# main.net
KiCad netlist of a schematic drawn in Altium Designer
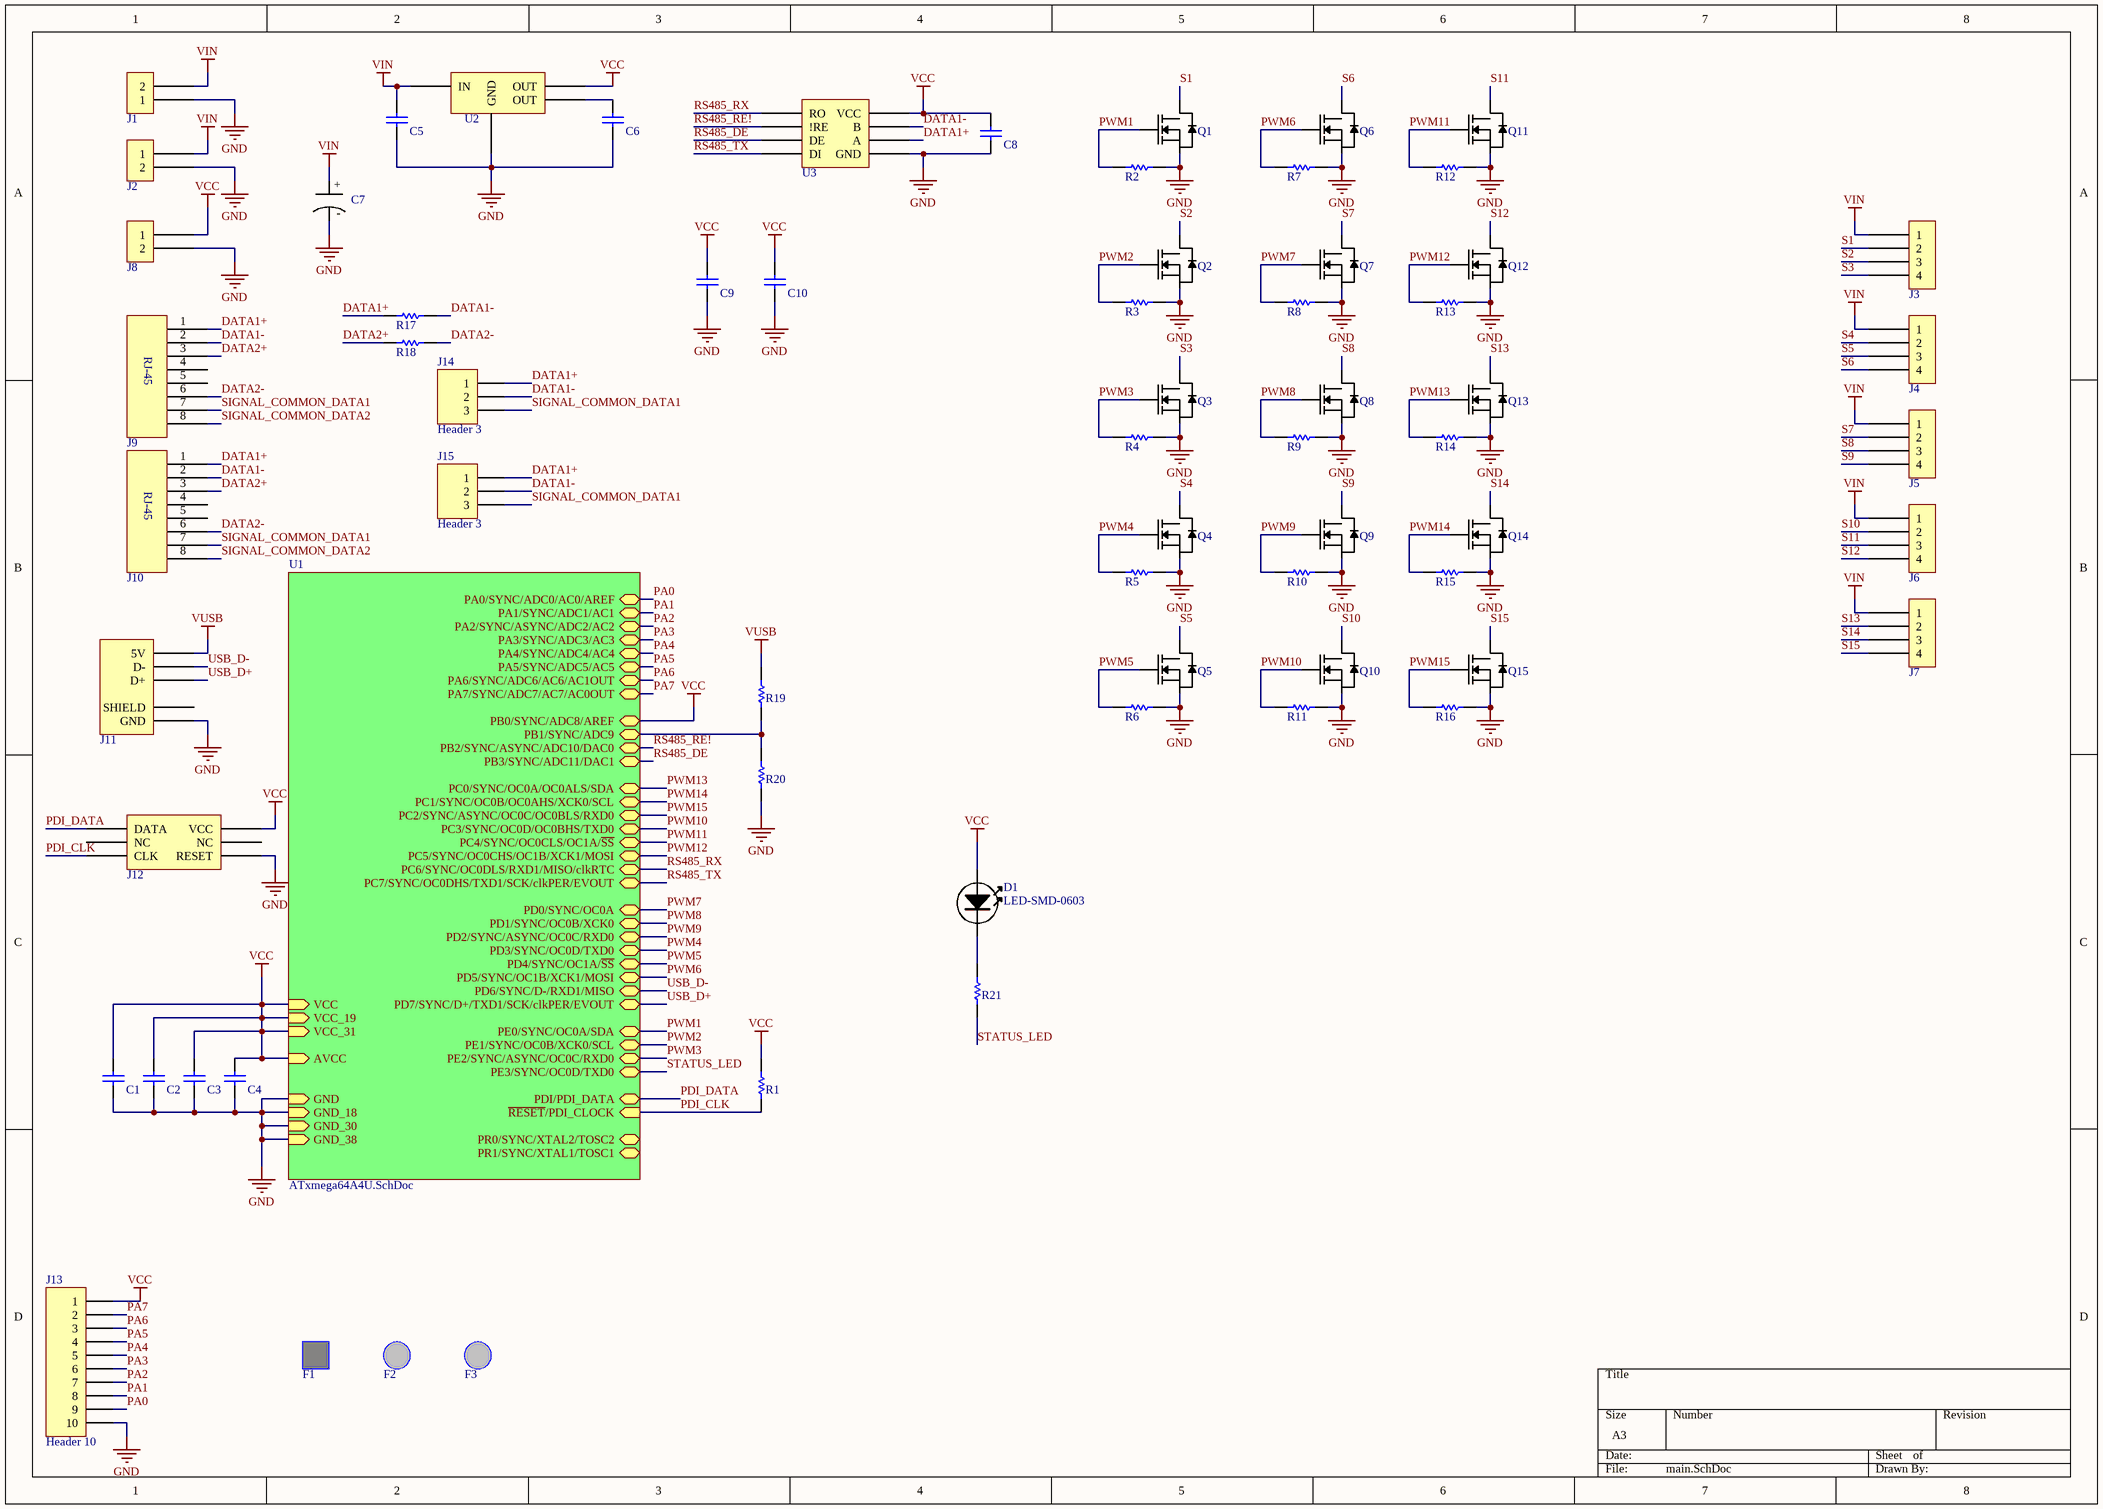
[diagram p0: main.SchDoc]

(export (version "E")
  (design (tool "Eeschema 10.0.6"))
  (components
    (comp (ref "C1")
      (value "CAP 3.3nF 10V 0805(2012)")
      (footprint "CAPC0805(2012)145_M")
      (description "CAP 3.3nF 10V ±1% 0805 (2012 Metric) Thickness 1.45mm SMD")
      (fields (field (name "TOLERANCE") "±1%"))
      (libsource (lib "Altium Content Vault") (part "CAP"))
    )
    (comp (ref "C2")
      (value "CAP 3.3nF 10V 0805(2012)")
      (footprint "CAPC0805(2012)145_M")
      (description "CAP 3.3nF 10V ±1% 0805 (2012 Metric) Thickness 1.45mm SMD")
      (fields (field (name "TOLERANCE") "±1%"))
      (libsource (lib "Altium Content Vault") (part "CAP"))
    )
    (comp (ref "C3")
      (value "CAP 3.3nF 10V 0805(2012)")
      (footprint "CAPC0805(2012)145_M")
      (description "CAP 3.3nF 10V ±1% 0805 (2012 Metric) Thickness 1.45mm SMD")
      (fields (field (name "TOLERANCE") "±1%"))
      (libsource (lib "Altium Content Vault") (part "CAP"))
    )
    (comp (ref "C4")
      (value "CAP 3.3nF 10V 0805(2012)")
      (footprint "CAPC0805(2012)145_M")
      (description "CAP 3.3nF 10V ±1% 0805 (2012 Metric) Thickness 1.45mm SMD")
      (fields (field (name "TOLERANCE") "±1%"))
      (libsource (lib "Altium Content Vault") (part "CAP"))
    )
    (comp (ref "C5")
      (value "CAP 1uF 16V 1210(3225)")
      (footprint "CAPC1210(3225)155_N")
      (description "CAP 1uF 16V ±5% 1210 (3225 Metric) Thickness 1.45mm SMD")
      (fields (field (name "TOLERANCE") "±5%"))
      (libsource (lib "Altium Content Vault") (part "CAP"))
    )
    (comp (ref "C6")
      (value "CAP 10uF 6.3V 1210(3225)")
      (footprint "CAPC1210(3225)170_L")
      (description "CAP 10uF 6.3V ±10% 1210 (3225 Metric) Thickness 1.7mm SMD")
      (fields (field (name "TOLERANCE") "±10%"))
      (libsource (lib "Altium Content Vault") (part "CAP"))
    )
    (comp (ref "C7")
      (value "ELECTROLYTIC-CAP-220uF")
      (footprint "ELECTROLYTIC-220uF")
      (libsource (lib "capacitors") (part "ELECTROLYTIC-CAP-220uF"))
    )
    (comp (ref "C8")
      (value "CAP 3.3nF 10V 0805(2012)")
      (footprint "CAPC0805(2012)145_M")
      (description "CAP 3.3nF 10V ±1% 0805 (2012 Metric) Thickness 1.45mm SMD")
      (fields (field (name "TOLERANCE") "±1%"))
      (libsource (lib "Altium Content Vault") (part "CAP"))
    )
    (comp (ref "C9")
      (value "CAP 10uF 6.3V 1210(3225)")
      (footprint "CAPC1210(3225)170_L")
      (description "CAP 10uF 6.3V ±10% 1210 (3225 Metric) Thickness 1.7mm SMD")
      (fields (field (name "TOLERANCE") "±10%"))
      (libsource (lib "Altium Content Vault") (part "CMP-1038-02188-1"))
    )
    (comp (ref "C10")
      (value "CAP 10uF 6.3V 1210(3225)")
      (footprint "CAPC1210(3225)170_L")
      (description "CAP 10uF 6.3V ±10% 1210 (3225 Metric) Thickness 1.7mm SMD")
      (fields (field (name "TOLERANCE") "±10%"))
      (libsource (lib "Altium Content Vault") (part "CMP-1038-02188-1"))
    )
    (comp (ref "D1")
      (value "LED-SMD-0603")
      (footprint "LED-0603")
      (description "SMD Led 0603")
      (libsource (lib "Omegav Vault") (part "LED-0603"))
    )
    (comp (ref "F1")
      (value "Fiducial square")
      (footprint "FIDU-SQUARE")
      (libsource (lib "fiducials") (part "FIDUCIAL_SQUARE"))
    )
    (comp (ref "F2")
      (value "Fiducial round")
      (footprint "FIDU-ROUND")
      (libsource (lib "fiducials") (part "FIDUCIAL_ROUND"))
    )
    (comp (ref "F3")
      (value "Fiducial round")
      (footprint "FIDU-ROUND")
      (libsource (lib "fiducials") (part "FIDUCIAL_ROUND"))
    )
    (comp (ref "J1")
      (value "PLUGGABLE-TERMINAL-2")
      (footprint "PLUG_TERMINAL_2")
      (libsource (lib "") (part "PLUGGABLE-TERMINAL-2_1"))
    )
    (comp (ref "J2")
      (value "PLUGGABLE-TERMINAL-2")
      (footprint "PLUG_TERMINAL_2")
      (libsource (lib "connectors") (part "PLUGGABLE-TERMINAL-2"))
    )
    (comp (ref "J3")
      (value "PLUGGABLE-TERMINAL-4")
      (footprint "PLUG_TERMINAL_4")
      (libsource (lib "connectors") (part "PLUGGABLE-TERMINAL-4"))
    )
    (comp (ref "J4")
      (value "PLUGGABLE-TERMINAL-4")
      (footprint "PLUG_TERMINAL_4")
      (libsource (lib "connectors") (part "PLUGGABLE-TERMINAL-4"))
    )
    (comp (ref "J5")
      (value "PLUGGABLE-TERMINAL-4")
      (footprint "PLUG_TERMINAL_4")
      (libsource (lib "connectors") (part "PLUGGABLE-TERMINAL-4"))
    )
    (comp (ref "J6")
      (value "PLUGGABLE-TERMINAL-4")
      (footprint "PLUG_TERMINAL_4")
      (libsource (lib "connectors") (part "PLUGGABLE-TERMINAL-4"))
    )
    (comp (ref "J7")
      (value "PLUGGABLE-TERMINAL-4")
      (footprint "PLUG_TERMINAL_4")
      (libsource (lib "connectors") (part "PLUGGABLE-TERMINAL-4"))
    )
    (comp (ref "J8")
      (value "PLUGGABLE-TERMINAL-2")
      (footprint "PLUG_TERMINAL_2")
      (libsource (lib "connectors") (part "PLUGGABLE-TERMINAL-2"))
    )
    (comp (ref "J9")
      (value "RJ-45 Connector")
      (footprint "RJ-45")
      (description "RJ-45 Ethernet Connector")
      (fields (field (name "TOLERANCE") "1"))
      (libsource (lib "Omegav Vault") (part "RJ-45"))
    )
    (comp (ref "J10")
      (value "RJ-45 Connector")
      (footprint "RJ-45")
      (description "RJ-45 Ethernet Connector")
      (fields (field (name "TOLERANCE") "1"))
      (libsource (lib "Omegav Vault") (part "RJ-45"))
    )
    (comp (ref "J11")
      (value "USB-MINI")
      (footprint "USB-mini")
      (description "USB-Mini Connector")
      (fields (field (name "TOLERANCE") "1"))
      (libsource (lib "Omegav Vault") (part "USB-mini"))
    )
    (comp (ref "J12")
      (value "PDI")
      (footprint "HEADER_SMD_3x2_50MIL")
      (libsource (lib "connectors") (part "PDI"))
    )
    (comp (ref "J13")
      (value "Header 10")
      (footprint "HDR1X10")
      (description "Header, 10-Pin")
      (fields (field (name "PUBLISHER") "Altium Limited"))
      (libsource (lib "Miscellaneous Connectors") (part "Header 10"))
    )
    (comp (ref "J14")
      (value "Header 3")
      (footprint "HDR1X3")
      (description "Header, 3-Pin")
      (fields (field (name "PUBLISHER") "Altium Limited"))
      (libsource (lib "Miscellaneous Connectors") (part "Header 3"))
    )
    (comp (ref "J15")
      (value "Header 3")
      (footprint "HDR1X3")
      (description "Header, 3-Pin")
      (fields (field (name "PUBLISHER") "Altium Limited"))
      (libsource (lib "Miscellaneous Connectors") (part "Header 3"))
    )
    (comp (ref "Q1")
      (value "TSM2314CX")
      (footprint "SOT95P280X130-3N")
      (description "MOSFET 4.9A max switching load")
      (libsource (lib "transistors") (part "TSM2314CX"))
    )
    (comp (ref "Q2")
      (value "TSM2314CX")
      (footprint "SOT95P280X130-3N")
      (description "MOSFET 4.9A max switching load")
      (libsource (lib "transistors") (part "TSM2314CX"))
    )
    (comp (ref "Q3")
      (value "TSM2314CX")
      (footprint "SOT95P280X130-3N")
      (description "MOSFET 4.9A max switching load")
      (libsource (lib "transistors") (part "TSM2314CX"))
    )
    (comp (ref "Q4")
      (value "TSM2314CX")
      (footprint "SOT95P280X130-3N")
      (description "MOSFET 4.9A max switching load")
      (libsource (lib "transistors") (part "TSM2314CX"))
    )
    (comp (ref "Q5")
      (value "TSM2314CX")
      (footprint "SOT95P280X130-3N")
      (description "MOSFET 4.9A max switching load")
      (libsource (lib "transistors") (part "TSM2314CX"))
    )
    (comp (ref "Q6")
      (value "TSM2314CX")
      (footprint "SOT95P280X130-3N")
      (description "MOSFET 4.9A max switching load")
      (libsource (lib "transistors") (part "TSM2314CX"))
    )
    (comp (ref "Q7")
      (value "TSM2314CX")
      (footprint "SOT95P280X130-3N")
      (description "MOSFET 4.9A max switching load")
      (libsource (lib "transistors") (part "TSM2314CX"))
    )
    (comp (ref "Q8")
      (value "TSM2314CX")
      (footprint "SOT95P280X130-3N")
      (description "MOSFET 4.9A max switching load")
      (libsource (lib "transistors") (part "TSM2314CX"))
    )
    (comp (ref "Q9")
      (value "TSM2314CX")
      (footprint "SOT95P280X130-3N")
      (description "MOSFET 4.9A max switching load")
      (libsource (lib "transistors") (part "TSM2314CX"))
    )
    (comp (ref "Q10")
      (value "TSM2314CX")
      (footprint "SOT95P280X130-3N")
      (description "MOSFET 4.9A max switching load")
      (libsource (lib "transistors") (part "TSM2314CX"))
    )
    (comp (ref "Q11")
      (value "TSM2314CX")
      (footprint "SOT95P280X130-3N")
      (description "MOSFET 4.9A max switching load")
      (libsource (lib "transistors") (part "TSM2314CX"))
    )
    (comp (ref "Q12")
      (value "TSM2314CX")
      (footprint "SOT95P280X130-3N")
      (description "MOSFET 4.9A max switching load")
      (libsource (lib "transistors") (part "TSM2314CX"))
    )
    (comp (ref "Q13")
      (value "TSM2314CX")
      (footprint "SOT95P280X130-3N")
      (description "MOSFET 4.9A max switching load")
      (libsource (lib "transistors") (part "TSM2314CX"))
    )
    (comp (ref "Q14")
      (value "TSM2314CX")
      (footprint "SOT95P280X130-3N")
      (description "MOSFET 4.9A max switching load")
      (libsource (lib "transistors") (part "TSM2314CX"))
    )
    (comp (ref "Q15")
      (value "TSM2314CX")
      (footprint "SOT95P280X130-3N")
      (description "MOSFET 4.9A max switching load")
      (libsource (lib "transistors") (part "TSM2314CX"))
    )
    (comp (ref "R1")
      (value "10K 1% 0805(2012)")
      (footprint "RESC0805(2012)_M")
      (description "10K 0.125W 1% 0805 (2012 Metric)  SMD")
      (fields (field (name "TOLERANCE") "1 %") (field (name "POWER") "0.125 W"))
      (libsource (lib "Altium Content Vault") (part "RES"))
    )
    (comp (ref "R2")
      (value "10K 1% 0805(2012)")
      (footprint "RESC0805(2012)_M")
      (description "10K 0.125W 1% 0805 (2012 Metric)  SMD")
      (fields (field (name "TOLERANCE") "1 %") (field (name "POWER") "0.125 W"))
      (libsource (lib "Altium Content Vault") (part "RES"))
    )
    (comp (ref "R3")
      (value "10K 1% 0805(2012)")
      (footprint "RESC0805(2012)_M")
      (description "10K 0.125W 1% 0805 (2012 Metric)  SMD")
      (fields (field (name "TOLERANCE") "1 %") (field (name "POWER") "0.125 W"))
      (libsource (lib "Altium Content Vault") (part "RES"))
    )
    (comp (ref "R4")
      (value "10K 1% 0805(2012)")
      (footprint "RESC0805(2012)_M")
      (description "10K 0.125W 1% 0805 (2012 Metric)  SMD")
      (fields (field (name "TOLERANCE") "1 %") (field (name "POWER") "0.125 W"))
      (libsource (lib "Altium Content Vault") (part "RES"))
    )
    (comp (ref "R5")
      (value "10K 1% 0805(2012)")
      (footprint "RESC0805(2012)_M")
      (description "10K 0.125W 1% 0805 (2012 Metric)  SMD")
      (fields (field (name "TOLERANCE") "1 %") (field (name "POWER") "0.125 W"))
      (libsource (lib "Altium Content Vault") (part "RES"))
    )
    (comp (ref "R6")
      (value "10K 1% 0805(2012)")
      (footprint "RESC0805(2012)_M")
      (description "10K 0.125W 1% 0805 (2012 Metric)  SMD")
      (fields (field (name "TOLERANCE") "1 %") (field (name "POWER") "0.125 W"))
      (libsource (lib "Altium Content Vault") (part "RES"))
    )
    (comp (ref "R7")
      (value "10K 1% 0805(2012)")
      (footprint "RESC0805(2012)_M")
      (description "10K 0.125W 1% 0805 (2012 Metric)  SMD")
      (fields (field (name "TOLERANCE") "1 %") (field (name "POWER") "0.125 W"))
      (libsource (lib "Altium Content Vault") (part "RES"))
    )
    (comp (ref "R8")
      (value "10K 1% 0805(2012)")
      (footprint "RESC0805(2012)_M")
      (description "10K 0.125W 1% 0805 (2012 Metric)  SMD")
      (fields (field (name "TOLERANCE") "1 %") (field (name "POWER") "0.125 W"))
      (libsource (lib "Altium Content Vault") (part "RES"))
    )
    (comp (ref "R9")
      (value "10K 1% 0805(2012)")
      (footprint "RESC0805(2012)_M")
      (description "10K 0.125W 1% 0805 (2012 Metric)  SMD")
      (fields (field (name "TOLERANCE") "1 %") (field (name "POWER") "0.125 W"))
      (libsource (lib "Altium Content Vault") (part "RES"))
    )
    (comp (ref "R10")
      (value "10K 1% 0805(2012)")
      (footprint "RESC0805(2012)_M")
      (description "10K 0.125W 1% 0805 (2012 Metric)  SMD")
      (fields (field (name "TOLERANCE") "1 %") (field (name "POWER") "0.125 W"))
      (libsource (lib "Altium Content Vault") (part "RES"))
    )
    (comp (ref "R11")
      (value "10K 1% 0805(2012)")
      (footprint "RESC0805(2012)_M")
      (description "10K 0.125W 1% 0805 (2012 Metric)  SMD")
      (fields (field (name "TOLERANCE") "1 %") (field (name "POWER") "0.125 W"))
      (libsource (lib "Altium Content Vault") (part "RES"))
    )
    (comp (ref "R12")
      (value "10K 1% 0805(2012)")
      (footprint "RESC0805(2012)_M")
      (description "10K 0.125W 1% 0805 (2012 Metric)  SMD")
      (fields (field (name "TOLERANCE") "1 %") (field (name "POWER") "0.125 W"))
      (libsource (lib "Altium Content Vault") (part "RES"))
    )
    (comp (ref "R13")
      (value "10K 1% 0805(2012)")
      (footprint "RESC0805(2012)_M")
      (description "10K 0.125W 1% 0805 (2012 Metric)  SMD")
      (fields (field (name "TOLERANCE") "1 %") (field (name "POWER") "0.125 W"))
      (libsource (lib "Altium Content Vault") (part "RES"))
    )
    (comp (ref "R14")
      (value "10K 1% 0805(2012)")
      (footprint "RESC0805(2012)_M")
      (description "10K 0.125W 1% 0805 (2012 Metric)  SMD")
      (fields (field (name "TOLERANCE") "1 %") (field (name "POWER") "0.125 W"))
      (libsource (lib "Altium Content Vault") (part "RES"))
    )
    (comp (ref "R15")
      (value "10K 1% 0805(2012)")
      (footprint "RESC0805(2012)_M")
      (description "10K 0.125W 1% 0805 (2012 Metric)  SMD")
      (fields (field (name "TOLERANCE") "1 %") (field (name "POWER") "0.125 W"))
      (libsource (lib "Altium Content Vault") (part "RES"))
    )
    (comp (ref "R16")
      (value "10K 1% 0805(2012)")
      (footprint "RESC0805(2012)_M")
      (description "10K 0.125W 1% 0805 (2012 Metric)  SMD")
      (fields (field (name "TOLERANCE") "1 %") (field (name "POWER") "0.125 W"))
      (libsource (lib "Altium Content Vault") (part "RES"))
    )
    (comp (ref "R17")
      (value "120R 1% 0805(2012)")
      (footprint "RESC0805(2012)_M")
      (description "120R 0.125W 1% 0805 (2012 Metric)  SMD")
      (fields (field (name "TOLERANCE") "1 %") (field (name "POWER") "0.125 W"))
      (libsource (lib "Altium Content Vault") (part "RES"))
    )
    (comp (ref "R18")
      (value "120R 1% 0805(2012)")
      (footprint "RESC0805(2012)_M")
      (description "120R 0.125W 1% 0805 (2012 Metric)  SMD")
      (fields (field (name "TOLERANCE") "1 %") (field (name "POWER") "0.125 W"))
      (libsource (lib "Altium Content Vault") (part "RES"))
    )
    (comp (ref "R19")
      (value "10K 1% 0805(2012)")
      (footprint "RESC0805(2012)_M")
      (description "10K 0.125W 1% 0805 (2012 Metric)  SMD")
      (fields (field (name "TOLERANCE") "1 %") (field (name "POWER") "0.125 W"))
      (libsource (lib "Altium Content Vault") (part "RES"))
    )
    (comp (ref "R20")
      (value "15K 1% 0805(2012)")
      (footprint "RESC0805(2012)_L")
      (description "15K 0.125W 1% 0805 (2012 Metric)  SMD")
      (fields (field (name "POWER") "0.125 W") (field (name "TOLERANCE") "1 %"))
      (libsource (lib "Altium Content Vault") (part "RES"))
    )
    (comp (ref "R21")
      (value "200R 1% 0805(2012)")
      (footprint "RESC0805(2012)_L")
      (description "200R 0.125W 1% 0805 (2012 Metric)  SMD")
      (fields (field (name "POWER") "0.125 W") (field (name "TOLERANCE") "1 %"))
      (libsource (lib "Altium Content Vault") (part "RES"))
    )
    (comp (ref "U2")
      (value "TLV1117")
      (footprint "SOT230P700X180-4N")
      (description "3.3V Linear Regulator")
      (libsource (lib "Omegav Vault") (part "TLV1117"))
    )
    (comp (ref "U3")
      (value "MAX3485")
      (footprint "SOP127P600X175-8N")
      (libsource (lib "ics") (part "MAX3485"))
    )
  )
  (nets
    (net (code "1") (name "/DATA1+") (class "Default")
      (node (ref "J10") (pin "1") (pinfunction "1_1") (pintype "passive"))
      (node (ref "J14") (pin "1") (pinfunction "1_1") (pintype "passive"))
      (node (ref "J15") (pin "1") (pinfunction "1_1") (pintype "passive"))
      (node (ref "J9") (pin "1") (pinfunction "1_1") (pintype "passive"))
      (node (ref "R17") (pin "1") (pinfunction "1_1") (pintype "passive"))
      (node (ref "U3") (pin "6") (pinfunction "A_6") (pintype "passive"))
    )
    (net (code "2") (name "/DATA1-") (class "Default")
      (node (ref "J10") (pin "2") (pinfunction "2_2") (pintype "passive"))
      (node (ref "J14") (pin "2") (pinfunction "2_2") (pintype "passive"))
      (node (ref "J15") (pin "2") (pinfunction "2_2") (pintype "passive"))
      (node (ref "J9") (pin "2") (pinfunction "2_2") (pintype "passive"))
      (node (ref "R17") (pin "2") (pinfunction "2_2") (pintype "passive"))
      (node (ref "U3") (pin "7") (pinfunction "B_7") (pintype "passive"))
    )
    (net (code "3") (name "/DATA2+") (class "Default")
      (node (ref "J10") (pin "3") (pinfunction "3_3") (pintype "passive"))
      (node (ref "J9") (pin "3") (pinfunction "3_3") (pintype "passive"))
      (node (ref "R18") (pin "1") (pinfunction "1_1") (pintype "passive"))
    )
    (net (code "4") (name "/DATA2-") (class "Default")
      (node (ref "J10") (pin "6") (pinfunction "6_6") (pintype "passive"))
      (node (ref "J9") (pin "6") (pinfunction "6_6") (pintype "passive"))
      (node (ref "R18") (pin "2") (pinfunction "2_2") (pintype "passive"))
    )
    (net (code "5") (name "/PA0") (class "Default")
      (node (ref "J13") (pin "9") (pinfunction "9_9") (pintype "passive"))
    )
    (net (code "6") (name "/PA1") (class "Default")
      (node (ref "J13") (pin "8") (pinfunction "8_8") (pintype "passive"))
    )
    (net (code "7") (name "/PA2") (class "Default")
      (node (ref "J13") (pin "7") (pinfunction "7_7") (pintype "passive"))
    )
    (net (code "8") (name "/PA3") (class "Default")
      (node (ref "J13") (pin "6") (pinfunction "6_6") (pintype "passive"))
    )
    (net (code "9") (name "/PA4") (class "Default")
      (node (ref "J13") (pin "5") (pinfunction "5_5") (pintype "passive"))
    )
    (net (code "10") (name "/PA5") (class "Default")
      (node (ref "J13") (pin "4") (pinfunction "4_4") (pintype "passive"))
    )
    (net (code "11") (name "/PA6") (class "Default")
      (node (ref "J13") (pin "3") (pinfunction "3_3") (pintype "passive"))
    )
    (net (code "12") (name "/PA7") (class "Default")
      (node (ref "J13") (pin "2") (pinfunction "2_2") (pintype "passive"))
    )
    (net (code "13") (name "/PB1{slash}SYNC{slash}ADC9") (class "Default")
      (node (ref "R19") (pin "1") (pinfunction "1_1") (pintype "passive"))
      (node (ref "R20") (pin "2") (pinfunction "2_2") (pintype "passive"))
    )
    (net (code "14") (name "/PDI_CLK") (class "Default")
      (node (ref "J12") (pin "5") (pinfunction "CLK_5") (pintype "passive"))
      (node (ref "R1") (pin "1") (pinfunction "1_1") (pintype "passive"))
    )
    (net (code "15") (name "/PDI_DATA") (class "Default")
      (node (ref "J12") (pin "1") (pinfunction "DATA_1") (pintype "passive"))
    )
    (net (code "18") (name "/PWM1") (class "Default")
      (node (ref "Q1") (pin "1") (pinfunction "G_1") (pintype "passive"))
      (node (ref "R2") (pin "1") (pinfunction "1_1") (pintype "passive"))
    )
    (net (code "19") (name "/PWM2") (class "Default")
      (node (ref "Q2") (pin "1") (pinfunction "G_1") (pintype "passive"))
      (node (ref "R3") (pin "1") (pinfunction "1_1") (pintype "passive"))
    )
    (net (code "20") (name "/PWM3") (class "Default")
      (node (ref "Q3") (pin "1") (pinfunction "G_1") (pintype "passive"))
      (node (ref "R4") (pin "1") (pinfunction "1_1") (pintype "passive"))
    )
    (net (code "21") (name "/PWM4") (class "Default")
      (node (ref "Q4") (pin "1") (pinfunction "G_1") (pintype "passive"))
      (node (ref "R5") (pin "1") (pinfunction "1_1") (pintype "passive"))
    )
    (net (code "22") (name "/PWM5") (class "Default")
      (node (ref "Q5") (pin "1") (pinfunction "G_1") (pintype "passive"))
      (node (ref "R6") (pin "1") (pinfunction "1_1") (pintype "passive"))
    )
    (net (code "23") (name "/PWM6") (class "Default")
      (node (ref "Q6") (pin "1") (pinfunction "G_1") (pintype "passive"))
      (node (ref "R7") (pin "1") (pinfunction "1_1") (pintype "passive"))
    )
    (net (code "24") (name "/PWM7") (class "Default")
      (node (ref "Q7") (pin "1") (pinfunction "G_1") (pintype "passive"))
      (node (ref "R8") (pin "1") (pinfunction "1_1") (pintype "passive"))
    )
    (net (code "25") (name "/PWM8") (class "Default")
      (node (ref "Q8") (pin "1") (pinfunction "G_1") (pintype "passive"))
      (node (ref "R9") (pin "1") (pinfunction "1_1") (pintype "passive"))
    )
    (net (code "26") (name "/PWM9") (class "Default")
      (node (ref "Q9") (pin "1") (pinfunction "G_1") (pintype "passive"))
      (node (ref "R10") (pin "1") (pinfunction "1_1") (pintype "passive"))
    )
    (net (code "27") (name "/PWM10") (class "Default")
      (node (ref "Q10") (pin "1") (pinfunction "G_1") (pintype "passive"))
      (node (ref "R11") (pin "1") (pinfunction "1_1") (pintype "passive"))
    )
    (net (code "28") (name "/PWM11") (class "Default")
      (node (ref "Q11") (pin "1") (pinfunction "G_1") (pintype "passive"))
      (node (ref "R12") (pin "1") (pinfunction "1_1") (pintype "passive"))
    )
    (net (code "29") (name "/PWM12") (class "Default")
      (node (ref "Q12") (pin "1") (pinfunction "G_1") (pintype "passive"))
      (node (ref "R13") (pin "1") (pinfunction "1_1") (pintype "passive"))
    )
    (net (code "30") (name "/PWM13") (class "Default")
      (node (ref "Q13") (pin "1") (pinfunction "G_1") (pintype "passive"))
      (node (ref "R14") (pin "1") (pinfunction "1_1") (pintype "passive"))
    )
    (net (code "31") (name "/PWM14") (class "Default")
      (node (ref "Q14") (pin "1") (pinfunction "G_1") (pintype "passive"))
      (node (ref "R15") (pin "1") (pinfunction "1_1") (pintype "passive"))
    )
    (net (code "32") (name "/PWM15") (class "Default")
      (node (ref "Q15") (pin "1") (pinfunction "G_1") (pintype "passive"))
      (node (ref "R16") (pin "1") (pinfunction "1_1") (pintype "passive"))
    )
    (net (code "33") (name "/RS485_DE") (class "Default")
      (node (ref "U3") (pin "3") (pinfunction "DE_3") (pintype "passive"))
    )
    (net (code "34") (name "/RS485_RE!") (class "Default")
      (node (ref "U3") (pin "2") (pinfunction "!RE_2") (pintype "passive"))
    )
    (net (code "35") (name "/RS485_RX") (class "Default")
      (node (ref "U3") (pin "1") (pinfunction "RO_1") (pintype "passive"))
    )
    (net (code "36") (name "/RS485_TX") (class "Default")
      (node (ref "U3") (pin "4") (pinfunction "DI_4") (pintype "passive"))
    )
    (net (code "37") (name "/S1") (class "Default")
      (node (ref "J3") (pin "2") (pinfunction "2_2") (pintype "passive"))
      (node (ref "Q1") (pin "3") (pinfunction "D_3") (pintype "passive"))
    )
    (net (code "38") (name "/S2") (class "Default")
      (node (ref "J3") (pin "3") (pinfunction "3_3") (pintype "passive"))
      (node (ref "Q2") (pin "3") (pinfunction "D_3") (pintype "passive"))
    )
    (net (code "39") (name "/S3") (class "Default")
      (node (ref "J3") (pin "4") (pinfunction "4_4") (pintype "passive"))
      (node (ref "Q3") (pin "3") (pinfunction "D_3") (pintype "passive"))
    )
    (net (code "40") (name "/S4") (class "Default")
      (node (ref "J4") (pin "2") (pinfunction "2_2") (pintype "passive"))
      (node (ref "Q4") (pin "3") (pinfunction "D_3") (pintype "passive"))
    )
    (net (code "41") (name "/S5") (class "Default")
      (node (ref "J4") (pin "3") (pinfunction "3_3") (pintype "passive"))
      (node (ref "Q5") (pin "3") (pinfunction "D_3") (pintype "passive"))
    )
    (net (code "42") (name "/S6") (class "Default")
      (node (ref "J4") (pin "4") (pinfunction "4_4") (pintype "passive"))
      (node (ref "Q6") (pin "3") (pinfunction "D_3") (pintype "passive"))
    )
    (net (code "43") (name "/S7") (class "Default")
      (node (ref "J5") (pin "2") (pinfunction "2_2") (pintype "passive"))
      (node (ref "Q7") (pin "3") (pinfunction "D_3") (pintype "passive"))
    )
    (net (code "44") (name "/S8") (class "Default")
      (node (ref "J5") (pin "3") (pinfunction "3_3") (pintype "passive"))
      (node (ref "Q8") (pin "3") (pinfunction "D_3") (pintype "passive"))
    )
    (net (code "45") (name "/S9") (class "Default")
      (node (ref "J5") (pin "4") (pinfunction "4_4") (pintype "passive"))
      (node (ref "Q9") (pin "3") (pinfunction "D_3") (pintype "passive"))
    )
    (net (code "46") (name "/S10") (class "Default")
      (node (ref "J6") (pin "2") (pinfunction "2_2") (pintype "passive"))
      (node (ref "Q10") (pin "3") (pinfunction "D_3") (pintype "passive"))
    )
    (net (code "47") (name "/S11") (class "Default")
      (node (ref "J6") (pin "3") (pinfunction "3_3") (pintype "passive"))
      (node (ref "Q11") (pin "3") (pinfunction "D_3") (pintype "passive"))
    )
    (net (code "48") (name "/S12") (class "Default")
      (node (ref "J6") (pin "4") (pinfunction "4_4") (pintype "passive"))
      (node (ref "Q12") (pin "3") (pinfunction "D_3") (pintype "passive"))
    )
    (net (code "49") (name "/S13") (class "Default")
      (node (ref "J7") (pin "2") (pinfunction "2_2") (pintype "passive"))
      (node (ref "Q13") (pin "3") (pinfunction "D_3") (pintype "passive"))
    )
    (net (code "50") (name "/S14") (class "Default")
      (node (ref "J7") (pin "3") (pinfunction "3_3") (pintype "passive"))
      (node (ref "Q14") (pin "3") (pinfunction "D_3") (pintype "passive"))
    )
    (net (code "51") (name "/S15") (class "Default")
      (node (ref "J7") (pin "4") (pinfunction "4_4") (pintype "passive"))
      (node (ref "Q15") (pin "3") (pinfunction "D_3") (pintype "passive"))
    )
    (net (code "52") (name "/SIGNAL_COMMON_DATA1") (class "Default")
      (node (ref "J10") (pin "7") (pinfunction "7_7") (pintype "passive"))
      (node (ref "J14") (pin "3") (pinfunction "3_3") (pintype "passive"))
      (node (ref "J15") (pin "3") (pinfunction "3_3") (pintype "passive"))
      (node (ref "J9") (pin "7") (pinfunction "7_7") (pintype "passive"))
    )
    (net (code "53") (name "/SIGNAL_COMMON_DATA2") (class "Default")
      (node (ref "J10") (pin "8") (pinfunction "8_8") (pintype "passive"))
      (node (ref "J9") (pin "8") (pinfunction "8_8") (pintype "passive"))
    )
    (net (code "54") (name "/STATUS_LED") (class "Default")
      (node (ref "R21") (pin "1") (pinfunction "1_1") (pintype "passive"))
    )
    (net (code "55") (name "/USB_D+") (class "Default")
      (node (ref "J11") (pin "3") (pinfunction "D+_3") (pintype "passive"))
    )
    (net (code "56") (name "/USB_D-") (class "Default")
      (node (ref "J11") (pin "2") (pinfunction "D-_2") (pintype "passive"))
    )
    (net (code "57") (name "GND") (class "Default")
      (node (ref "C1") (pin "1") (pinfunction "1_1") (pintype "passive"))
      (node (ref "C10") (pin "1") (pinfunction "1_1") (pintype "passive"))
      (node (ref "C2") (pin "1") (pinfunction "1_1") (pintype "passive"))
      (node (ref "C3") (pin "1") (pinfunction "1_1") (pintype "passive"))
      (node (ref "C4") (pin "1") (pinfunction "1_1") (pintype "passive"))
      (node (ref "C5") (pin "1") (pinfunction "1_1") (pintype "passive"))
      (node (ref "C6") (pin "1") (pinfunction "1_1") (pintype "passive"))
      (node (ref "C7") (pin "2") (pinfunction "-_2") (pintype "passive"))
      (node (ref "C8") (pin "1") (pinfunction "1_1") (pintype "passive"))
      (node (ref "C9") (pin "1") (pinfunction "1_1") (pintype "passive"))
      (node (ref "J1") (pin "1") (pinfunction "1_1") (pintype "passive"))
      (node (ref "J11") (pin "5") (pinfunction "GND_5") (pintype "passive"))
      (node (ref "J12") (pin "6") (pinfunction "RESET_6") (pintype "passive"))
      (node (ref "J13") (pin "10") (pinfunction "10_10") (pintype "passive"))
      (node (ref "J2") (pin "2") (pinfunction "2_2") (pintype "passive"))
      (node (ref "J8") (pin "2") (pinfunction "2_2") (pintype "passive"))
      (node (ref "Q1") (pin "2") (pinfunction "S_2") (pintype "passive"))
      (node (ref "Q10") (pin "2") (pinfunction "S_2") (pintype "passive"))
      (node (ref "Q11") (pin "2") (pinfunction "S_2") (pintype "passive"))
      (node (ref "Q12") (pin "2") (pinfunction "S_2") (pintype "passive"))
      (node (ref "Q13") (pin "2") (pinfunction "S_2") (pintype "passive"))
      (node (ref "Q14") (pin "2") (pinfunction "S_2") (pintype "passive"))
      (node (ref "Q15") (pin "2") (pinfunction "S_2") (pintype "passive"))
      (node (ref "Q2") (pin "2") (pinfunction "S_2") (pintype "passive"))
      (node (ref "Q3") (pin "2") (pinfunction "S_2") (pintype "passive"))
      (node (ref "Q4") (pin "2") (pinfunction "S_2") (pintype "passive"))
      (node (ref "Q5") (pin "2") (pinfunction "S_2") (pintype "passive"))
      (node (ref "Q6") (pin "2") (pinfunction "S_2") (pintype "passive"))
      (node (ref "Q7") (pin "2") (pinfunction "S_2") (pintype "passive"))
      (node (ref "Q8") (pin "2") (pinfunction "S_2") (pintype "passive"))
      (node (ref "Q9") (pin "2") (pinfunction "S_2") (pintype "passive"))
      (node (ref "R10") (pin "2") (pinfunction "2_2") (pintype "passive"))
      (node (ref "R11") (pin "2") (pinfunction "2_2") (pintype "passive"))
      (node (ref "R12") (pin "2") (pinfunction "2_2") (pintype "passive"))
      (node (ref "R13") (pin "2") (pinfunction "2_2") (pintype "passive"))
      (node (ref "R14") (pin "2") (pinfunction "2_2") (pintype "passive"))
      (node (ref "R15") (pin "2") (pinfunction "2_2") (pintype "passive"))
      (node (ref "R16") (pin "2") (pinfunction "2_2") (pintype "passive"))
      (node (ref "R2") (pin "2") (pinfunction "2_2") (pintype "passive"))
      (node (ref "R20") (pin "1") (pinfunction "1_1") (pintype "passive"))
      (node (ref "R3") (pin "2") (pinfunction "2_2") (pintype "passive"))
      (node (ref "R4") (pin "2") (pinfunction "2_2") (pintype "passive"))
      (node (ref "R5") (pin "2") (pinfunction "2_2") (pintype "passive"))
      (node (ref "R6") (pin "2") (pinfunction "2_2") (pintype "passive"))
      (node (ref "R7") (pin "2") (pinfunction "2_2") (pintype "passive"))
      (node (ref "R8") (pin "2") (pinfunction "2_2") (pintype "passive"))
      (node (ref "R9") (pin "2") (pinfunction "2_2") (pintype "passive"))
      (node (ref "U2") (pin "1") (pinfunction "GND_1") (pintype "passive"))
      (node (ref "U3") (pin "5") (pinfunction "GND_5") (pintype "passive"))
    )
    (net (code "58") (name "Net-(C6-Pad2)") (class "Default")
      (node (ref "C6") (pin "2") (pinfunction "2_2") (pintype "passive"))
      (node (ref "U2") (pin "2") (pinfunction "OUT_2") (pintype "passive"))
    )
    (net (code "59") (name "Net-(D1-Pad2)") (class "Default")
      (node (ref "D1") (pin "2") (pintype "passive"))
      (node (ref "R21") (pin "2") (pinfunction "2_2") (pintype "passive"))
    )
    (net (code "60") (name "VCC") (class "Default")
      (node (ref "C1") (pin "2") (pinfunction "2_2") (pintype "passive"))
      (node (ref "C10") (pin "2") (pinfunction "2_2") (pintype "passive"))
      (node (ref "C2") (pin "2") (pinfunction "2_2") (pintype "passive"))
      (node (ref "C3") (pin "2") (pinfunction "2_2") (pintype "passive"))
      (node (ref "C4") (pin "2") (pinfunction "2_2") (pintype "passive"))
      (node (ref "C8") (pin "2") (pinfunction "2_2") (pintype "passive"))
      (node (ref "C9") (pin "2") (pinfunction "2_2") (pintype "passive"))
      (node (ref "D1") (pin "1") (pintype "passive"))
      (node (ref "J12") (pin "2") (pinfunction "VCC_2") (pintype "passive"))
      (node (ref "J13") (pin "1") (pinfunction "1_1") (pintype "passive"))
      (node (ref "J8") (pin "1") (pinfunction "1_1") (pintype "passive"))
      (node (ref "R1") (pin "2") (pinfunction "2_2") (pintype "passive"))
      (node (ref "U2") (pin "4") (pinfunction "OUT_4") (pintype "passive"))
      (node (ref "U3") (pin "8") (pinfunction "VCC_8") (pintype "passive"))
    )
    (net (code "61") (name "VIN") (class "Default")
      (node (ref "C5") (pin "2") (pinfunction "2_2") (pintype "passive"))
      (node (ref "C7") (pin "1") (pinfunction "+_1") (pintype "passive"))
      (node (ref "J1") (pin "2") (pinfunction "2_2") (pintype "passive"))
      (node (ref "J2") (pin "1") (pinfunction "1_1") (pintype "passive"))
      (node (ref "J3") (pin "1") (pinfunction "1_1") (pintype "passive"))
      (node (ref "J4") (pin "1") (pinfunction "1_1") (pintype "passive"))
      (node (ref "J5") (pin "1") (pinfunction "1_1") (pintype "passive"))
      (node (ref "J6") (pin "1") (pinfunction "1_1") (pintype "passive"))
      (node (ref "J7") (pin "1") (pinfunction "1_1") (pintype "passive"))
      (node (ref "U2") (pin "3") (pinfunction "IN_3") (pintype "passive"))
    )
    (net (code "62") (name "VUSB") (class "Default")
      (node (ref "J11") (pin "1") (pinfunction "5V_1") (pintype "passive"))
      (node (ref "R19") (pin "2") (pinfunction "2_2") (pintype "passive"))
    )
    (net (code "63") (name "unconnected-(J9-Pad4)") (class "Default")
      (node (ref "J9") (pin "4") (pinfunction "4_4") (pintype "passive"))
    )
    (net (code "64") (name "unconnected-(J9-Pad5)") (class "Default")
      (node (ref "J9") (pin "5") (pinfunction "5_5") (pintype "passive"))
    )
    (net (code "65") (name "unconnected-(J10-Pad4)") (class "Default")
      (node (ref "J10") (pin "4") (pinfunction "4_4") (pintype "passive"))
    )
    (net (code "66") (name "unconnected-(J10-Pad5)") (class "Default")
      (node (ref "J10") (pin "5") (pinfunction "5_5") (pintype "passive"))
    )
    (net (code "67") (name "unconnected-(J11-SHIELD-Pad0)") (class "Default")
      (node (ref "J11") (pin "0") (pinfunction "SHIELD_0") (pintype "power_in"))
    )
    (net (code "68") (name "unconnected-(J12-NC-Pad3)") (class "Default")
      (node (ref "J12") (pin "3") (pinfunction "NC_3") (pintype "passive"))
    )
    (net (code "69") (name "unconnected-(J12-NC-Pad4)") (class "Default")
      (node (ref "J12") (pin "4") (pinfunction "NC_4") (pintype "passive"))
    )
  )
)
